# ts6907.net
KiCad netlist of a schematic drawn in EAGLE
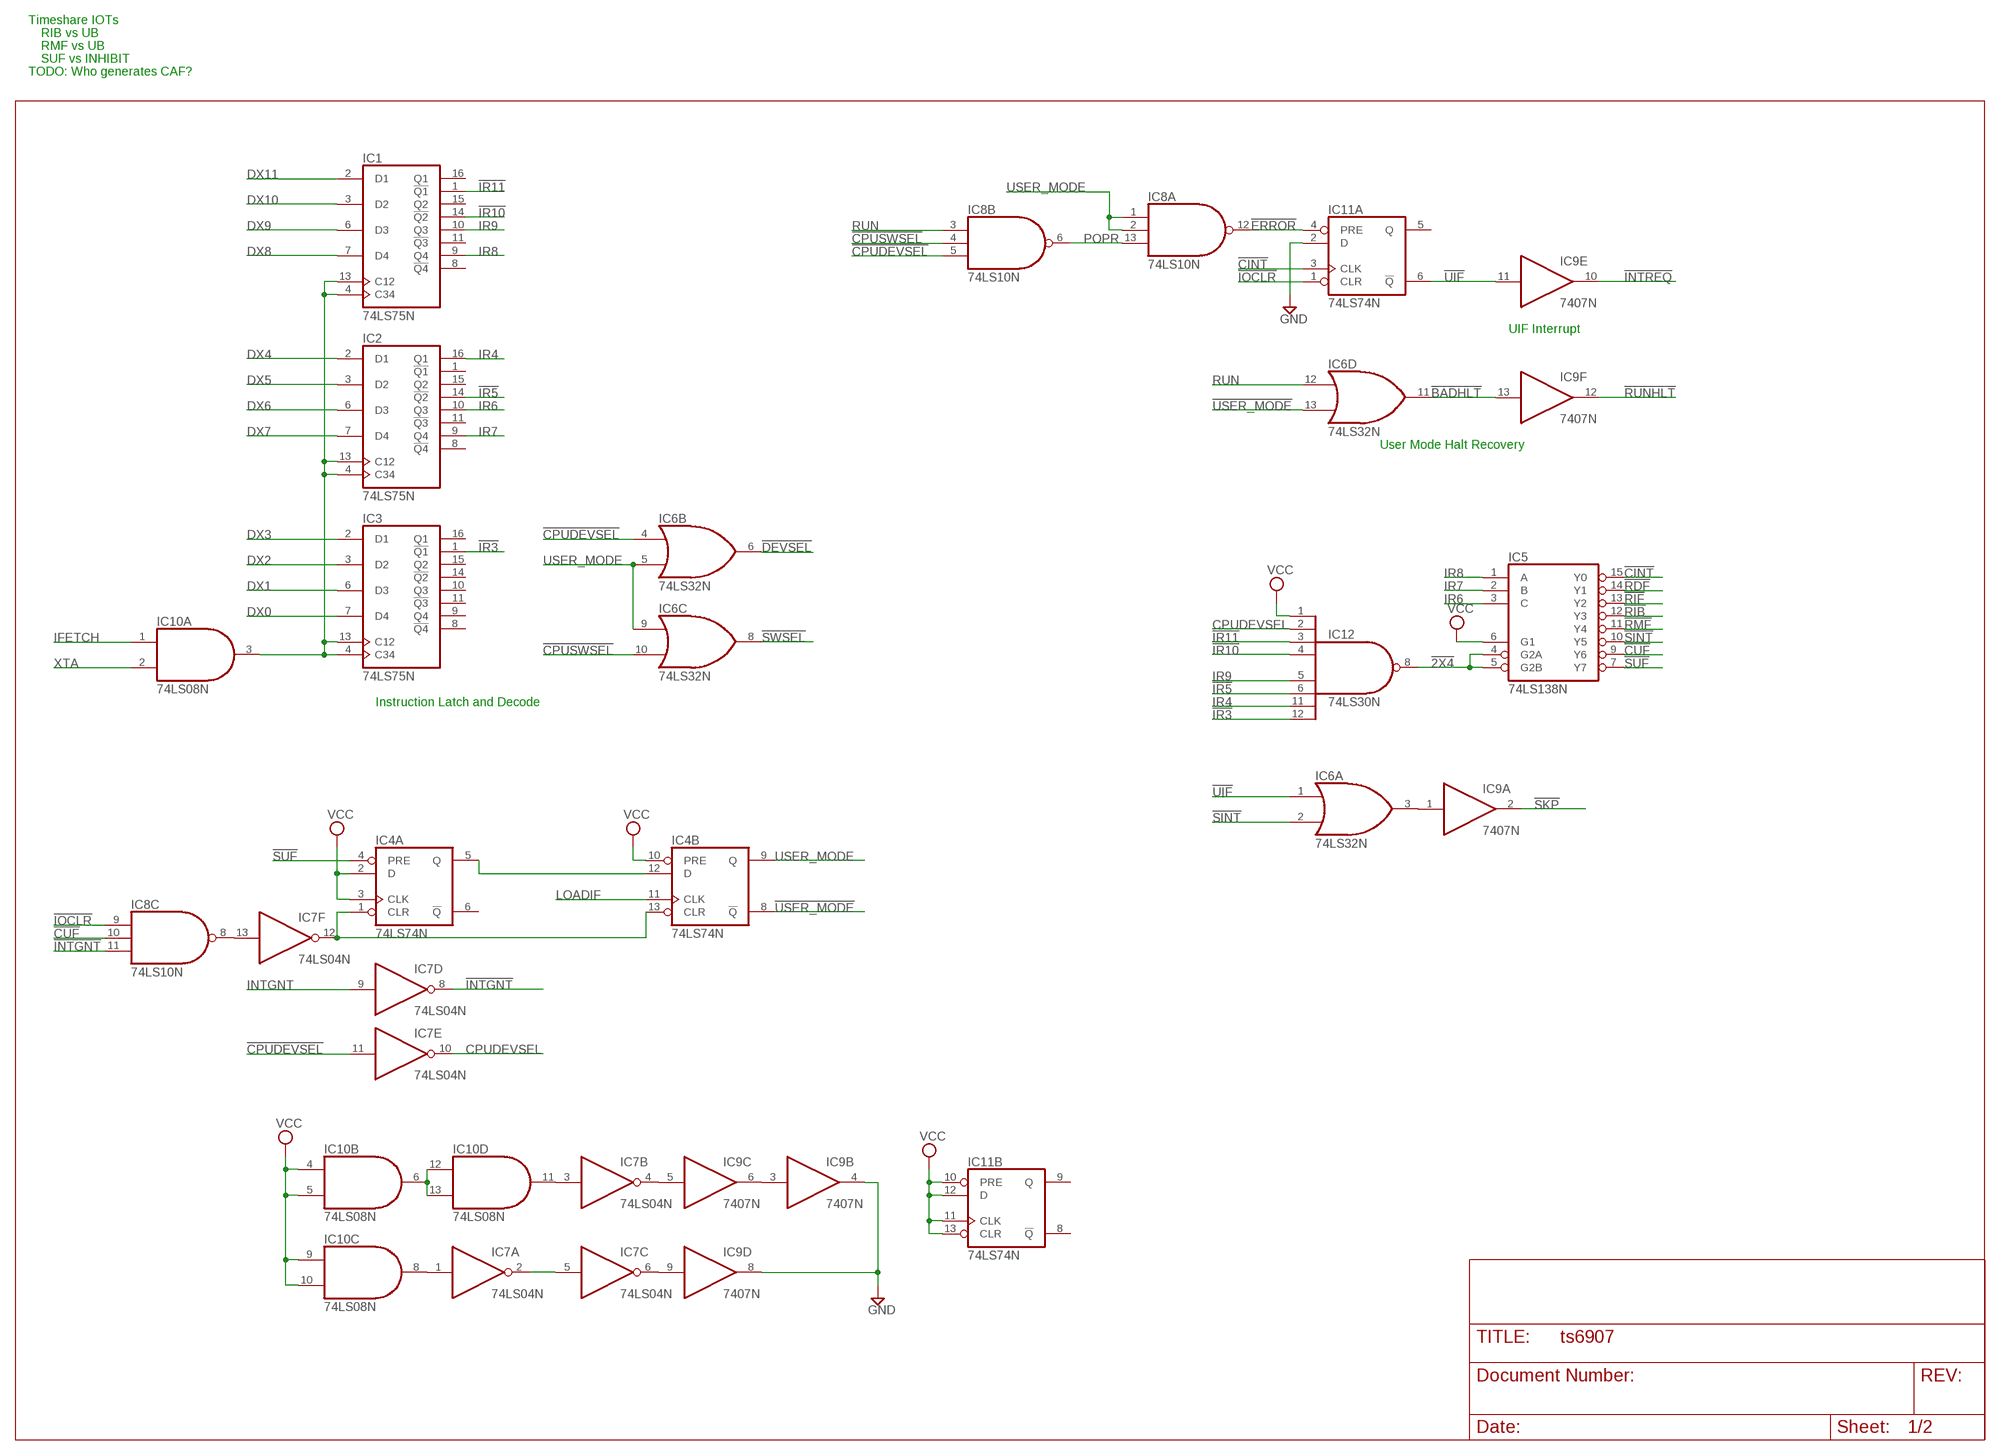
[diagram p0: schematic, sheet 1]
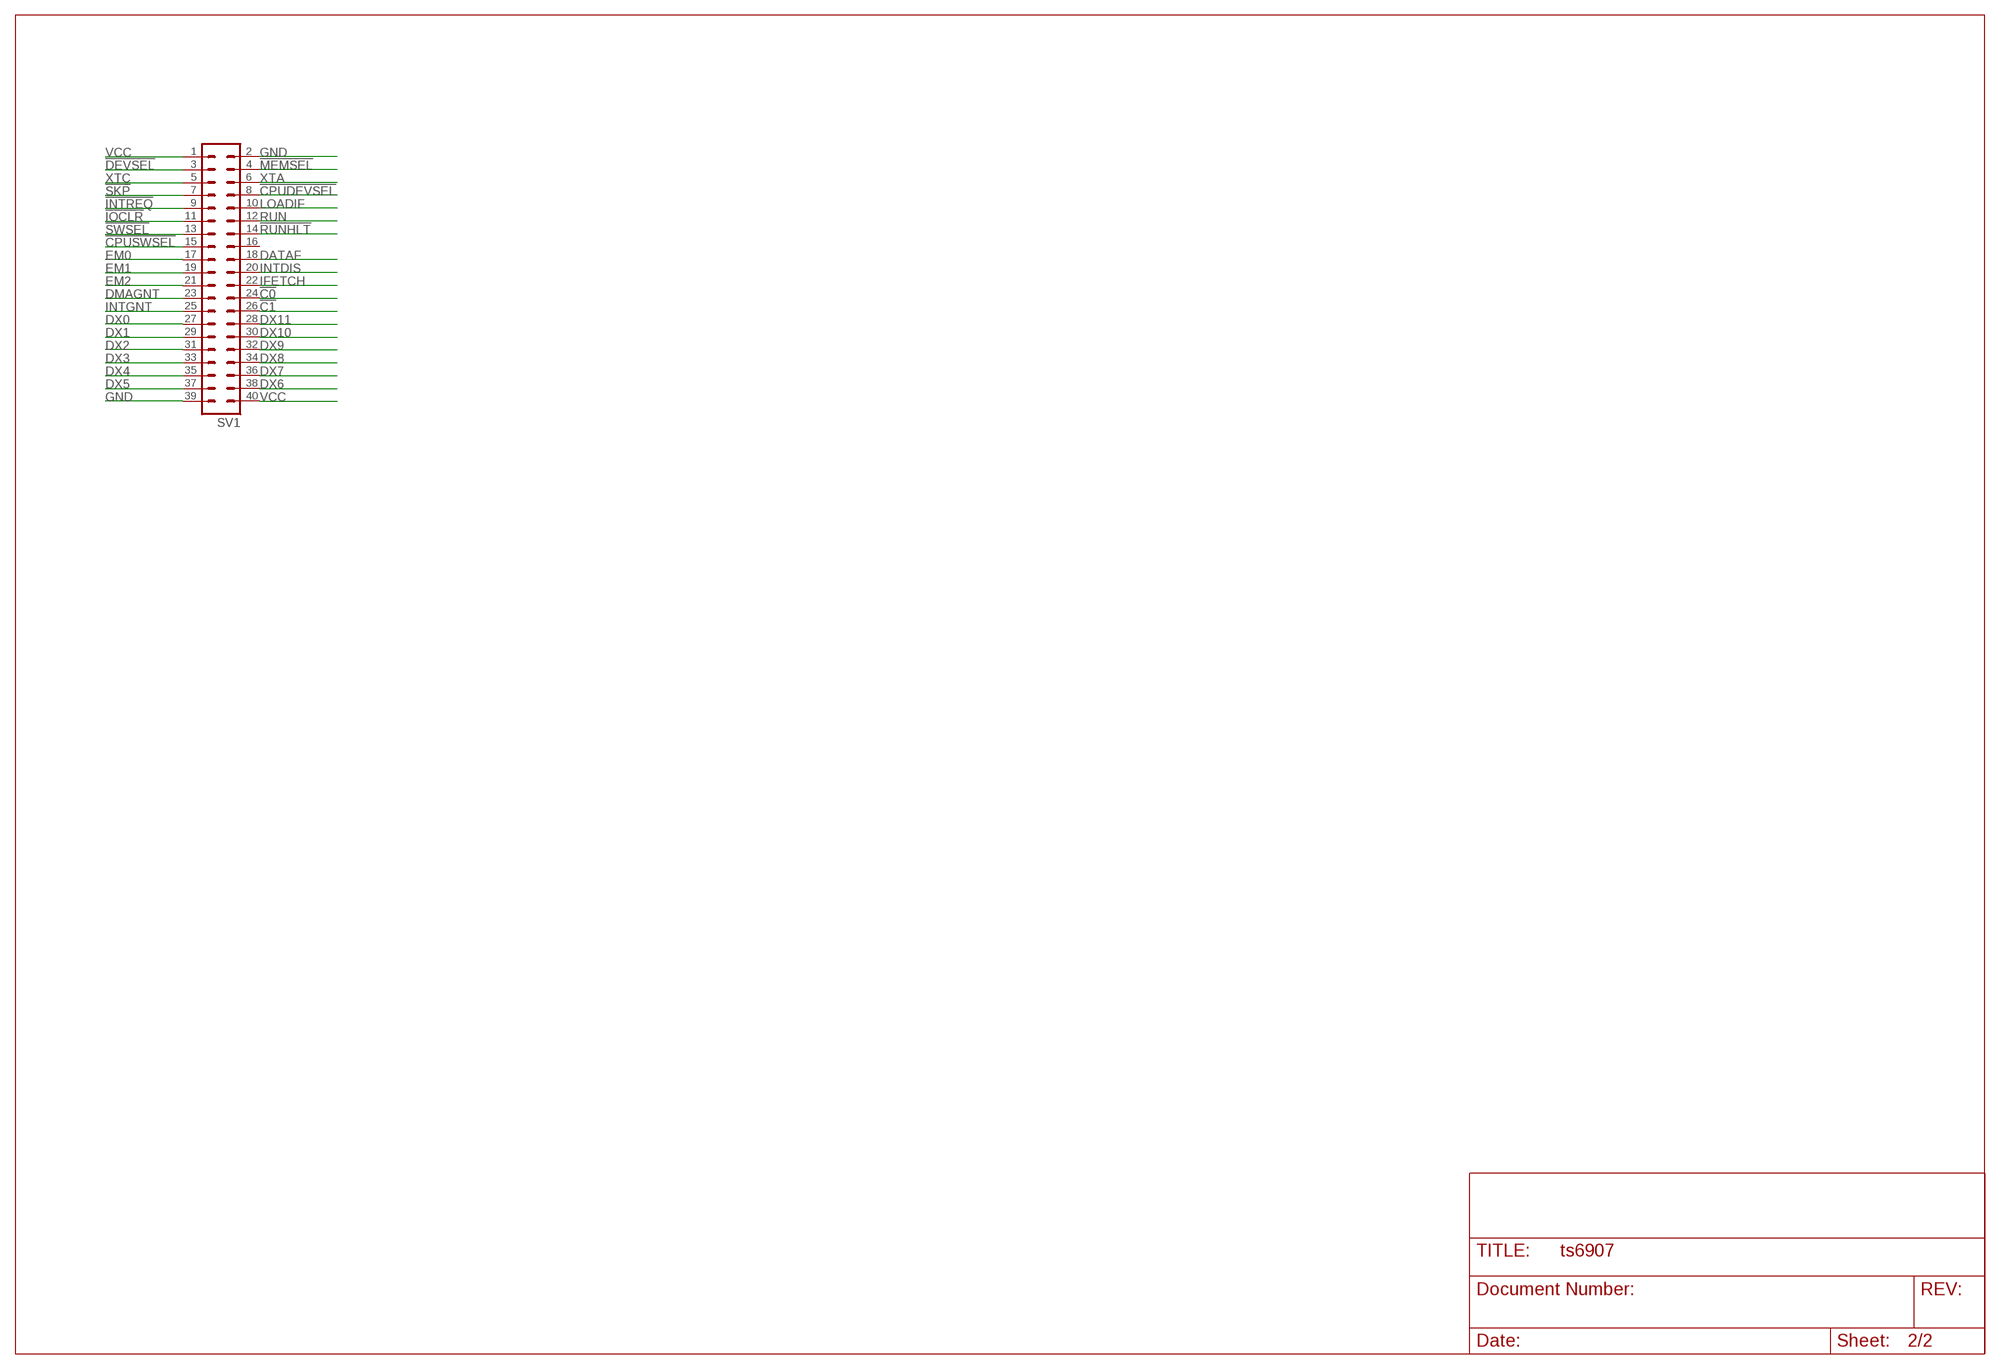
[diagram p1: schematic, sheet 2]

(export (version "E")
  (design (tool "Eeschema 10.0.6"))
  (components
    (comp (ref "SV1")
      (value "MA20-2")
      (footprint "eagle-import:MA20-2")
      (libsource (lib "eagle-import") (part "MA20-2"))
    )
    (comp (ref "IC1")
      (value "74LS75N")
      (footprint "eagle-import:DIL16")
      (libsource (lib "eagle-import") (part "7475NLS"))
    )
    (comp (ref "IC2")
      (value "74LS75N")
      (footprint "eagle-import:DIL16")
      (libsource (lib "eagle-import") (part "7475NLS"))
    )
    (comp (ref "IC3")
      (value "74LS75N")
      (footprint "eagle-import:DIL16")
      (libsource (lib "eagle-import") (part "7475NLS"))
    )
    (comp (ref "IC4")
      (value "74LS74N")
      (footprint "eagle-import:DIL14")
      (libsource (lib "eagle-import") (part "7474NLS"))
    )
    (comp (ref "IC5")
      (value "74LS138N")
      (footprint "eagle-import:DIL16")
      (libsource (lib "eagle-import") (part "74138NLS"))
    )
    (comp (ref "IC6")
      (value "74LS32N")
      (footprint "eagle-import:DIL14")
      (libsource (lib "eagle-import") (part "7432NLS"))
    )
    (comp (ref "IC7")
      (value "74LS04N")
      (footprint "eagle-import:DIL14")
      (libsource (lib "eagle-import") (part "7404NLS"))
    )
    (comp (ref "IC8")
      (value "74LS10N")
      (footprint "eagle-import:DIL14")
      (libsource (lib "eagle-import") (part "7410NLS"))
    )
    (comp (ref "IC9")
      (value "7407N")
      (footprint "eagle-import:DIL14")
      (libsource (lib "eagle-import") (part "7407N"))
    )
    (comp (ref "IC10")
      (value "74LS08N")
      (footprint "eagle-import:DIL14")
      (libsource (lib "eagle-import") (part "7408NLS"))
    )
    (comp (ref "IC11")
      (value "74LS74N")
      (footprint "eagle-import:DIL14")
      (libsource (lib "eagle-import") (part "7474NLS"))
    )
    (comp (ref "IC12")
      (value "74LS30N")
      (footprint "eagle-import:DIL14")
      (libsource (lib "eagle-import") (part "7430NLS"))
    )
  )
  (nets
    (net (code "1") (name "CPUDEVSEL") (class "Default")
      (node (ref "IC12") (pin "2") (pinfunction "I1_2") (pintype "input"))
      (node (ref "IC7") (pin "10") (pinfunction "O_10") (pintype "output"))
    )
    (net (code "2") (name "DATAF") (class "Default")
      (node (ref "SV1") (pin "18") (pinfunction "18_18") (pintype "passive"))
    )
    (net (code "3") (name "DMAGNT") (class "Default")
      (node (ref "SV1") (pin "23") (pinfunction "23_23") (pintype "passive"))
    )
    (net (code "4") (name "DX0") (class "Default")
      (node (ref "IC3") (pin "7") (pinfunction "D4_7") (pintype "input"))
      (node (ref "SV1") (pin "27") (pinfunction "27_27") (pintype "passive"))
    )
    (net (code "5") (name "DX1") (class "Default")
      (node (ref "IC3") (pin "6") (pinfunction "D3_6") (pintype "input"))
      (node (ref "SV1") (pin "29") (pinfunction "29_29") (pintype "passive"))
    )
    (net (code "6") (name "DX2") (class "Default")
      (node (ref "IC3") (pin "3") (pinfunction "D2_3") (pintype "input"))
      (node (ref "SV1") (pin "31") (pinfunction "31_31") (pintype "passive"))
    )
    (net (code "7") (name "DX3") (class "Default")
      (node (ref "IC3") (pin "2") (pinfunction "D1_2") (pintype "input"))
      (node (ref "SV1") (pin "33") (pinfunction "33_33") (pintype "passive"))
    )
    (net (code "8") (name "DX4") (class "Default")
      (node (ref "IC2") (pin "2") (pinfunction "D1_2") (pintype "input"))
      (node (ref "SV1") (pin "35") (pinfunction "35_35") (pintype "passive"))
    )
    (net (code "9") (name "DX5") (class "Default")
      (node (ref "IC2") (pin "3") (pinfunction "D2_3") (pintype "input"))
      (node (ref "SV1") (pin "37") (pinfunction "37_37") (pintype "passive"))
    )
    (net (code "10") (name "DX6") (class "Default")
      (node (ref "IC2") (pin "6") (pinfunction "D3_6") (pintype "input"))
      (node (ref "SV1") (pin "38") (pinfunction "38_38") (pintype "passive"))
    )
    (net (code "11") (name "DX7") (class "Default")
      (node (ref "IC2") (pin "7") (pinfunction "D4_7") (pintype "input"))
      (node (ref "SV1") (pin "36") (pinfunction "36_36") (pintype "passive"))
    )
    (net (code "12") (name "DX8") (class "Default")
      (node (ref "IC1") (pin "7") (pinfunction "D4_7") (pintype "input"))
      (node (ref "SV1") (pin "34") (pinfunction "34_34") (pintype "passive"))
    )
    (net (code "13") (name "DX9") (class "Default")
      (node (ref "IC1") (pin "6") (pinfunction "D3_6") (pintype "input"))
      (node (ref "SV1") (pin "32") (pinfunction "32_32") (pintype "passive"))
    )
    (net (code "14") (name "DX10") (class "Default")
      (node (ref "IC1") (pin "3") (pinfunction "D2_3") (pintype "input"))
      (node (ref "SV1") (pin "30") (pinfunction "30_30") (pintype "passive"))
    )
    (net (code "15") (name "DX11") (class "Default")
      (node (ref "IC1") (pin "2") (pinfunction "D1_2") (pintype "input"))
      (node (ref "SV1") (pin "28") (pinfunction "28_28") (pintype "passive"))
    )
    (net (code "16") (name "EM0") (class "Default")
      (node (ref "SV1") (pin "17") (pinfunction "17_17") (pintype "passive"))
    )
    (net (code "17") (name "EM1") (class "Default")
      (node (ref "SV1") (pin "19") (pinfunction "19_19") (pintype "passive"))
    )
    (net (code "18") (name "EM2") (class "Default")
      (node (ref "SV1") (pin "21") (pinfunction "21_21") (pintype "passive"))
    )
    (net (code "19") (name "GND") (class "Default")
      (node (ref "IC11") (pin "2") (pinfunction "D_2") (pintype "input"))
      (node (ref "IC9") (pin "4") (pinfunction "O_4") (pintype "open_collector"))
      (node (ref "IC9") (pin "8") (pinfunction "O_8") (pintype "open_collector"))
      (node (ref "SV1") (pin "2") (pinfunction "2_2") (pintype "passive"))
      (node (ref "SV1") (pin "39") (pinfunction "39_39") (pintype "passive"))
    )
    (net (code "20") (name "IFETCH") (class "Default")
      (node (ref "IC10") (pin "1") (pinfunction "I0_1") (pintype "input"))
      (node (ref "SV1") (pin "22") (pinfunction "22_22") (pintype "passive"))
    )
    (net (code "21") (name "INTDIS") (class "Default")
      (node (ref "SV1") (pin "20") (pinfunction "20_20") (pintype "passive"))
    )
    (net (code "22") (name "INTGNT") (class "Default")
      (node (ref "IC7") (pin "9") (pinfunction "I_9") (pintype "input"))
      (node (ref "SV1") (pin "25") (pinfunction "25_25") (pintype "passive"))
    )
    (net (code "23") (name "IR4") (class "Default")
      (node (ref "IC12") (pin "11") (pinfunction "I6_11") (pintype "input"))
      (node (ref "IC2") (pin "16") (pinfunction "Q1_16") (pintype "output"))
    )
    (net (code "24") (name "IR6") (class "Default")
      (node (ref "IC2") (pin "10") (pinfunction "Q3_10") (pintype "output"))
      (node (ref "IC5") (pin "3") (pinfunction "C_3") (pintype "input"))
    )
    (net (code "25") (name "IR7") (class "Default")
      (node (ref "IC2") (pin "9") (pinfunction "Q4_9") (pintype "output"))
      (node (ref "IC5") (pin "2") (pinfunction "B_2") (pintype "input"))
    )
    (net (code "26") (name "IR8") (class "Default")
      (node (ref "IC1") (pin "9") (pinfunction "Q4_9") (pintype "output"))
      (node (ref "IC5") (pin "1") (pinfunction "A_1") (pintype "input"))
    )
    (net (code "27") (name "IR9") (class "Default")
      (node (ref "IC1") (pin "10") (pinfunction "Q3_10") (pintype "output"))
      (node (ref "IC12") (pin "5") (pinfunction "I4_5") (pintype "input"))
    )
    (net (code "28") (name "LOADIF") (class "Default")
      (node (ref "IC4") (pin "11") (pinfunction "CLK_11") (pintype "input"))
      (node (ref "SV1") (pin "10") (pinfunction "10_10") (pintype "passive"))
    )
    (net (code "29") (name "Net-(IC4A-CLR)") (class "Default")
      (node (ref "IC4") (pin "1") (pinfunction "CLR_1") (pintype "input"))
      (node (ref "IC4") (pin "13") (pinfunction "CLR_13") (pintype "input"))
      (node (ref "IC7") (pin "12") (pinfunction "O_12") (pintype "output"))
    )
    (net (code "30") (name "Net-(IC4A-Q)") (class "Default")
      (node (ref "IC4") (pin "12") (pinfunction "D_12") (pintype "input"))
      (node (ref "IC4") (pin "5") (pinfunction "Q_5") (pintype "output"))
    )
    (net (code "31") (name "Net-(IC6A-O)") (class "Default")
      (node (ref "IC6") (pin "3") (pinfunction "O_3") (pintype "output"))
      (node (ref "IC9") (pin "1") (pinfunction "I_1") (pintype "input"))
    )
    (net (code "32") (name "Net-(IC7A-O)") (class "Default")
      (node (ref "IC7") (pin "2") (pinfunction "O_2") (pintype "output"))
      (node (ref "IC7") (pin "5") (pinfunction "I_5") (pintype "input"))
    )
    (net (code "33") (name "Net-(IC7B-O)") (class "Default")
      (node (ref "IC7") (pin "4") (pinfunction "O_4") (pintype "output"))
      (node (ref "IC9") (pin "5") (pinfunction "I_5") (pintype "input"))
    )
    (net (code "34") (name "Net-(IC7C-O)") (class "Default")
      (node (ref "IC7") (pin "6") (pinfunction "O_6") (pintype "output"))
      (node (ref "IC9") (pin "9") (pinfunction "I_9") (pintype "input"))
    )
    (net (code "35") (name "Net-(IC7F-I)") (class "Default")
      (node (ref "IC7") (pin "13") (pinfunction "I_13") (pintype "input"))
      (node (ref "IC8") (pin "8") (pinfunction "O_8") (pintype "output"))
    )
    (net (code "36") (name "Net-(IC9B-I)") (class "Default")
      (node (ref "IC9") (pin "3") (pinfunction "I_3") (pintype "input"))
      (node (ref "IC9") (pin "6") (pinfunction "O_6") (pintype "open_collector"))
    )
    (net (code "37") (name "Net-(IC10A-O)") (class "Default")
      (node (ref "IC1") (pin "13") (pinfunction "C12_13") (pintype "input"))
      (node (ref "IC1") (pin "4") (pinfunction "C34_4") (pintype "input"))
      (node (ref "IC10") (pin "3") (pinfunction "O_3") (pintype "output"))
      (node (ref "IC2") (pin "13") (pinfunction "C12_13") (pintype "input"))
      (node (ref "IC2") (pin "4") (pinfunction "C34_4") (pintype "input"))
      (node (ref "IC3") (pin "13") (pinfunction "C12_13") (pintype "input"))
      (node (ref "IC3") (pin "4") (pinfunction "C34_4") (pintype "input"))
    )
    (net (code "38") (name "Net-(IC10B-O)") (class "Default")
      (node (ref "IC10") (pin "12") (pinfunction "I0_12") (pintype "input"))
      (node (ref "IC10") (pin "13") (pinfunction "I1_13") (pintype "input"))
      (node (ref "IC10") (pin "6") (pinfunction "O_6") (pintype "output"))
    )
    (net (code "39") (name "Net-(IC10C-O)") (class "Default")
      (node (ref "IC10") (pin "8") (pinfunction "O_8") (pintype "output"))
      (node (ref "IC7") (pin "1") (pinfunction "I_1") (pintype "input"))
    )
    (net (code "40") (name "Net-(IC10D-O)") (class "Default")
      (node (ref "IC10") (pin "11") (pinfunction "O_11") (pintype "output"))
      (node (ref "IC7") (pin "3") (pinfunction "I_3") (pintype "input"))
    )
    (net (code "41") (name "POPR") (class "Default")
      (node (ref "IC8") (pin "13") (pinfunction "I2_13") (pintype "input"))
      (node (ref "IC8") (pin "6") (pinfunction "O_6") (pintype "output"))
    )
    (net (code "42") (name "RUN") (class "Default")
      (node (ref "IC6") (pin "12") (pinfunction "I0_12") (pintype "input"))
      (node (ref "IC8") (pin "3") (pinfunction "I0_3") (pintype "input"))
      (node (ref "SV1") (pin "12") (pinfunction "12_12") (pintype "passive"))
    )
    (net (code "43") (name "USER_MODE") (class "Default")
      (node (ref "IC4") (pin "9") (pinfunction "Q_9") (pintype "output"))
      (node (ref "IC6") (pin "5") (pinfunction "I1_5") (pintype "input"))
      (node (ref "IC6") (pin "9") (pinfunction "I0_9") (pintype "input"))
      (node (ref "IC8") (pin "1") (pinfunction "I0_1") (pintype "input"))
      (node (ref "IC8") (pin "2") (pinfunction "I1_2") (pintype "input"))
    )
    (net (code "44") (name "VCC") (class "Default")
      (node (ref "IC10") (pin "10") (pinfunction "I1_10") (pintype "input"))
      (node (ref "IC10") (pin "4") (pinfunction "I0_4") (pintype "input"))
      (node (ref "IC10") (pin "5") (pinfunction "I1_5") (pintype "input"))
      (node (ref "IC10") (pin "9") (pinfunction "I0_9") (pintype "input"))
      (node (ref "IC11") (pin "10") (pinfunction "PRE_10") (pintype "input"))
      (node (ref "IC11") (pin "11") (pinfunction "CLK_11") (pintype "input"))
      (node (ref "IC11") (pin "12") (pinfunction "D_12") (pintype "input"))
      (node (ref "IC11") (pin "13") (pinfunction "CLR_13") (pintype "input"))
      (node (ref "IC12") (pin "1") (pinfunction "I0_1") (pintype "input"))
      (node (ref "IC4") (pin "10") (pinfunction "PRE_10") (pintype "input"))
      (node (ref "IC4") (pin "2") (pinfunction "D_2") (pintype "input"))
      (node (ref "IC4") (pin "3") (pinfunction "CLK_3") (pintype "input"))
      (node (ref "IC5") (pin "6") (pinfunction "G1_6") (pintype "input"))
      (node (ref "SV1") (pin "1") (pinfunction "1_1") (pintype "passive"))
      (node (ref "SV1") (pin "40") (pinfunction "40_40") (pintype "passive"))
    )
    (net (code "45") (name "XTA") (class "Default")
      (node (ref "IC10") (pin "2") (pinfunction "I1_2") (pintype "input"))
      (node (ref "SV1") (pin "6") (pinfunction "6_6") (pintype "passive"))
    )
    (net (code "46") (name "XTC") (class "Default")
      (node (ref "SV1") (pin "5") (pinfunction "5_5") (pintype "passive"))
    )
    (net (code "47") (name "unconnected-(IC1A-Q1-Pad16)") (class "Default")
      (node (ref "IC1") (pin "16") (pinfunction "Q1_16") (pintype "output"))
    )
    (net (code "48") (name "unconnected-(IC1A-Q2-Pad15)") (class "Default")
      (node (ref "IC1") (pin "15") (pinfunction "Q2_15") (pintype "output"))
    )
    (net (code "49") (name "unconnected-(IC1A-~{Q3}-Pad11)") (class "Default")
      (node (ref "IC1") (pin "11") (pinfunction "~{Q3}_11") (pintype "output"))
    )
    (net (code "50") (name "unconnected-(IC1A-~{Q4}-Pad8)") (class "Default")
      (node (ref "IC1") (pin "8") (pinfunction "~{Q4}_8") (pintype "output"))
    )
    (net (code "51") (name "unconnected-(IC2A-Q2-Pad15)") (class "Default")
      (node (ref "IC2") (pin "15") (pinfunction "Q2_15") (pintype "output"))
    )
    (net (code "52") (name "unconnected-(IC2A-~{Q1}-Pad1)") (class "Default")
      (node (ref "IC2") (pin "1") (pinfunction "~{Q1}_1") (pintype "output"))
    )
    (net (code "53") (name "unconnected-(IC2A-~{Q3}-Pad11)") (class "Default")
      (node (ref "IC2") (pin "11") (pinfunction "~{Q3}_11") (pintype "output"))
    )
    (net (code "54") (name "unconnected-(IC2A-~{Q4}-Pad8)") (class "Default")
      (node (ref "IC2") (pin "8") (pinfunction "~{Q4}_8") (pintype "output"))
    )
    (net (code "55") (name "unconnected-(IC3A-Q1-Pad16)") (class "Default")
      (node (ref "IC3") (pin "16") (pinfunction "Q1_16") (pintype "output"))
    )
    (net (code "56") (name "unconnected-(IC3A-Q2-Pad15)") (class "Default")
      (node (ref "IC3") (pin "15") (pinfunction "Q2_15") (pintype "output"))
    )
    (net (code "57") (name "unconnected-(IC3A-Q3-Pad10)") (class "Default")
      (node (ref "IC3") (pin "10") (pinfunction "Q3_10") (pintype "output"))
    )
    (net (code "58") (name "unconnected-(IC3A-Q4-Pad9)") (class "Default")
      (node (ref "IC3") (pin "9") (pinfunction "Q4_9") (pintype "output"))
    )
    (net (code "59") (name "unconnected-(IC3A-~{Q2}-Pad14)") (class "Default")
      (node (ref "IC3") (pin "14") (pinfunction "~{Q2}_14") (pintype "output"))
    )
    (net (code "60") (name "unconnected-(IC3A-~{Q3}-Pad11)") (class "Default")
      (node (ref "IC3") (pin "11") (pinfunction "~{Q3}_11") (pintype "output"))
    )
    (net (code "61") (name "unconnected-(IC3A-~{Q4}-Pad8)") (class "Default")
      (node (ref "IC3") (pin "8") (pinfunction "~{Q4}_8") (pintype "output"))
    )
    (net (code "62") (name "unconnected-(IC4A-~{Q}-Pad6)") (class "Default")
      (node (ref "IC4") (pin "6") (pinfunction "~{Q}_6") (pintype "output"))
    )
    (net (code "63") (name "unconnected-(IC11A-Q-Pad5)") (class "Default")
      (node (ref "IC11") (pin "5") (pinfunction "Q_5") (pintype "output"))
    )
    (net (code "64") (name "unconnected-(IC11B-Q-Pad9)") (class "Default")
      (node (ref "IC11") (pin "9") (pinfunction "Q_9") (pintype "output"))
    )
    (net (code "65") (name "unconnected-(IC11B-~{Q}-Pad8)") (class "Default")
      (node (ref "IC11") (pin "8") (pinfunction "~{Q}_8") (pintype "output"))
    )
    (net (code "66") (name "unconnected-(SV1-Pad16)") (class "Default")
      (node (ref "SV1") (pin "16") (pinfunction "16_16") (pintype "passive"))
    )
    (net (code "67") (name "~{2X4}") (class "Default")
      (node (ref "IC12") (pin "8") (pinfunction "O_8") (pintype "output"))
      (node (ref "IC5") (pin "4") (pinfunction "G2A_4") (pintype "input"))
      (node (ref "IC5") (pin "5") (pinfunction "G2B_5") (pintype "input"))
    )
    (net (code "68") (name "~{BADHLT}") (class "Default")
      (node (ref "IC6") (pin "11") (pinfunction "O_11") (pintype "output"))
      (node (ref "IC9") (pin "13") (pinfunction "I_13") (pintype "input"))
    )
    (net (code "69") (name "~{C0}") (class "Default")
      (node (ref "SV1") (pin "24") (pinfunction "24_24") (pintype "passive"))
    )
    (net (code "70") (name "~{C1}") (class "Default")
      (node (ref "SV1") (pin "26") (pinfunction "26_26") (pintype "passive"))
    )
    (net (code "71") (name "~{CINT}") (class "Default")
      (node (ref "IC11") (pin "3") (pinfunction "CLK_3") (pintype "input"))
      (node (ref "IC5") (pin "15") (pinfunction "Y0_15") (pintype "output"))
    )
    (net (code "72") (name "~{CPUDEVSEL}") (class "Default")
      (node (ref "IC6") (pin "4") (pinfunction "I0_4") (pintype "input"))
      (node (ref "IC7") (pin "11") (pinfunction "I_11") (pintype "input"))
      (node (ref "IC8") (pin "5") (pinfunction "I2_5") (pintype "input"))
      (node (ref "SV1") (pin "8") (pinfunction "8_8") (pintype "passive"))
    )
    (net (code "73") (name "~{CPUSWSEL}") (class "Default")
      (node (ref "IC6") (pin "10") (pinfunction "I1_10") (pintype "input"))
      (node (ref "IC8") (pin "4") (pinfunction "I1_4") (pintype "input"))
      (node (ref "SV1") (pin "15") (pinfunction "15_15") (pintype "passive"))
    )
    (net (code "74") (name "~{CUF}") (class "Default")
      (node (ref "IC5") (pin "9") (pinfunction "Y6_9") (pintype "output"))
      (node (ref "IC8") (pin "10") (pinfunction "I1_10") (pintype "input"))
    )
    (net (code "75") (name "~{DEVSEL}") (class "Default")
      (node (ref "IC6") (pin "6") (pinfunction "O_6") (pintype "output"))
      (node (ref "SV1") (pin "3") (pinfunction "3_3") (pintype "passive"))
    )
    (net (code "76") (name "~{ERROR}") (class "Default")
      (node (ref "IC11") (pin "4") (pinfunction "PRE_4") (pintype "input"))
      (node (ref "IC8") (pin "12") (pinfunction "O_12") (pintype "output"))
    )
    (net (code "77") (name "~{INTGNT}") (class "Default")
      (node (ref "IC7") (pin "8") (pinfunction "O_8") (pintype "output"))
      (node (ref "IC8") (pin "11") (pinfunction "I2_11") (pintype "input"))
    )
    (net (code "78") (name "~{INTREQ}") (class "Default")
      (node (ref "IC9") (pin "10") (pinfunction "O_10") (pintype "open_collector"))
      (node (ref "SV1") (pin "9") (pinfunction "9_9") (pintype "passive"))
    )
    (net (code "79") (name "~{IOCLR}") (class "Default")
      (node (ref "IC11") (pin "1") (pinfunction "CLR_1") (pintype "input"))
      (node (ref "IC8") (pin "9") (pinfunction "I0_9") (pintype "input"))
      (node (ref "SV1") (pin "11") (pinfunction "11_11") (pintype "passive"))
    )
    (net (code "80") (name "~{IR3}") (class "Default")
      (node (ref "IC12") (pin "12") (pinfunction "I7_12") (pintype "input"))
      (node (ref "IC3") (pin "1") (pinfunction "~{Q1}_1") (pintype "output"))
    )
    (net (code "81") (name "~{IR5}") (class "Default")
      (node (ref "IC12") (pin "6") (pinfunction "I5_6") (pintype "input"))
      (node (ref "IC2") (pin "14") (pinfunction "~{Q2}_14") (pintype "output"))
    )
    (net (code "82") (name "~{IR10}") (class "Default")
      (node (ref "IC1") (pin "14") (pinfunction "~{Q2}_14") (pintype "output"))
      (node (ref "IC12") (pin "4") (pinfunction "I3_4") (pintype "input"))
    )
    (net (code "83") (name "~{IR11}") (class "Default")
      (node (ref "IC1") (pin "1") (pinfunction "~{Q1}_1") (pintype "output"))
      (node (ref "IC12") (pin "3") (pinfunction "I2_3") (pintype "input"))
    )
    (net (code "84") (name "~{MEMSEL}") (class "Default")
      (node (ref "SV1") (pin "4") (pinfunction "4_4") (pintype "passive"))
    )
    (net (code "85") (name "~{RDF}") (class "Default")
      (node (ref "IC5") (pin "14") (pinfunction "Y1_14") (pintype "output"))
    )
    (net (code "86") (name "~{RIB}") (class "Default")
      (node (ref "IC5") (pin "12") (pinfunction "Y3_12") (pintype "output"))
    )
    (net (code "87") (name "~{RIF}") (class "Default")
      (node (ref "IC5") (pin "13") (pinfunction "Y2_13") (pintype "output"))
    )
    (net (code "88") (name "~{RMF}") (class "Default")
      (node (ref "IC5") (pin "11") (pinfunction "Y4_11") (pintype "output"))
    )
    (net (code "89") (name "~{RUNHLT}") (class "Default")
      (node (ref "IC9") (pin "12") (pinfunction "O_12") (pintype "open_collector"))
      (node (ref "SV1") (pin "14") (pinfunction "14_14") (pintype "passive"))
    )
    (net (code "90") (name "~{SINT}") (class "Default")
      (node (ref "IC5") (pin "10") (pinfunction "Y5_10") (pintype "output"))
      (node (ref "IC6") (pin "2") (pinfunction "I1_2") (pintype "input"))
    )
    (net (code "91") (name "~{SKP}") (class "Default")
      (node (ref "IC9") (pin "2") (pinfunction "O_2") (pintype "open_collector"))
      (node (ref "SV1") (pin "7") (pinfunction "7_7") (pintype "passive"))
    )
    (net (code "92") (name "~{SUF}") (class "Default")
      (node (ref "IC4") (pin "4") (pinfunction "PRE_4") (pintype "input"))
      (node (ref "IC5") (pin "7") (pinfunction "Y7_7") (pintype "output"))
    )
    (net (code "93") (name "~{SWSEL}") (class "Default")
      (node (ref "IC6") (pin "8") (pinfunction "O_8") (pintype "output"))
      (node (ref "SV1") (pin "13") (pinfunction "13_13") (pintype "passive"))
    )
    (net (code "94") (name "~{UIF}") (class "Default")
      (node (ref "IC11") (pin "6") (pinfunction "~{Q}_6") (pintype "output"))
      (node (ref "IC6") (pin "1") (pinfunction "I0_1") (pintype "input"))
      (node (ref "IC9") (pin "11") (pinfunction "I_11") (pintype "input"))
    )
    (net (code "95") (name "~{USER_MODE}") (class "Default")
      (node (ref "IC4") (pin "8") (pinfunction "~{Q}_8") (pintype "output"))
      (node (ref "IC6") (pin "13") (pinfunction "I1_13") (pintype "input"))
    )
  )
)
